# LCD_board.net
KiCad netlist of a schematic drawn in Altium Designer
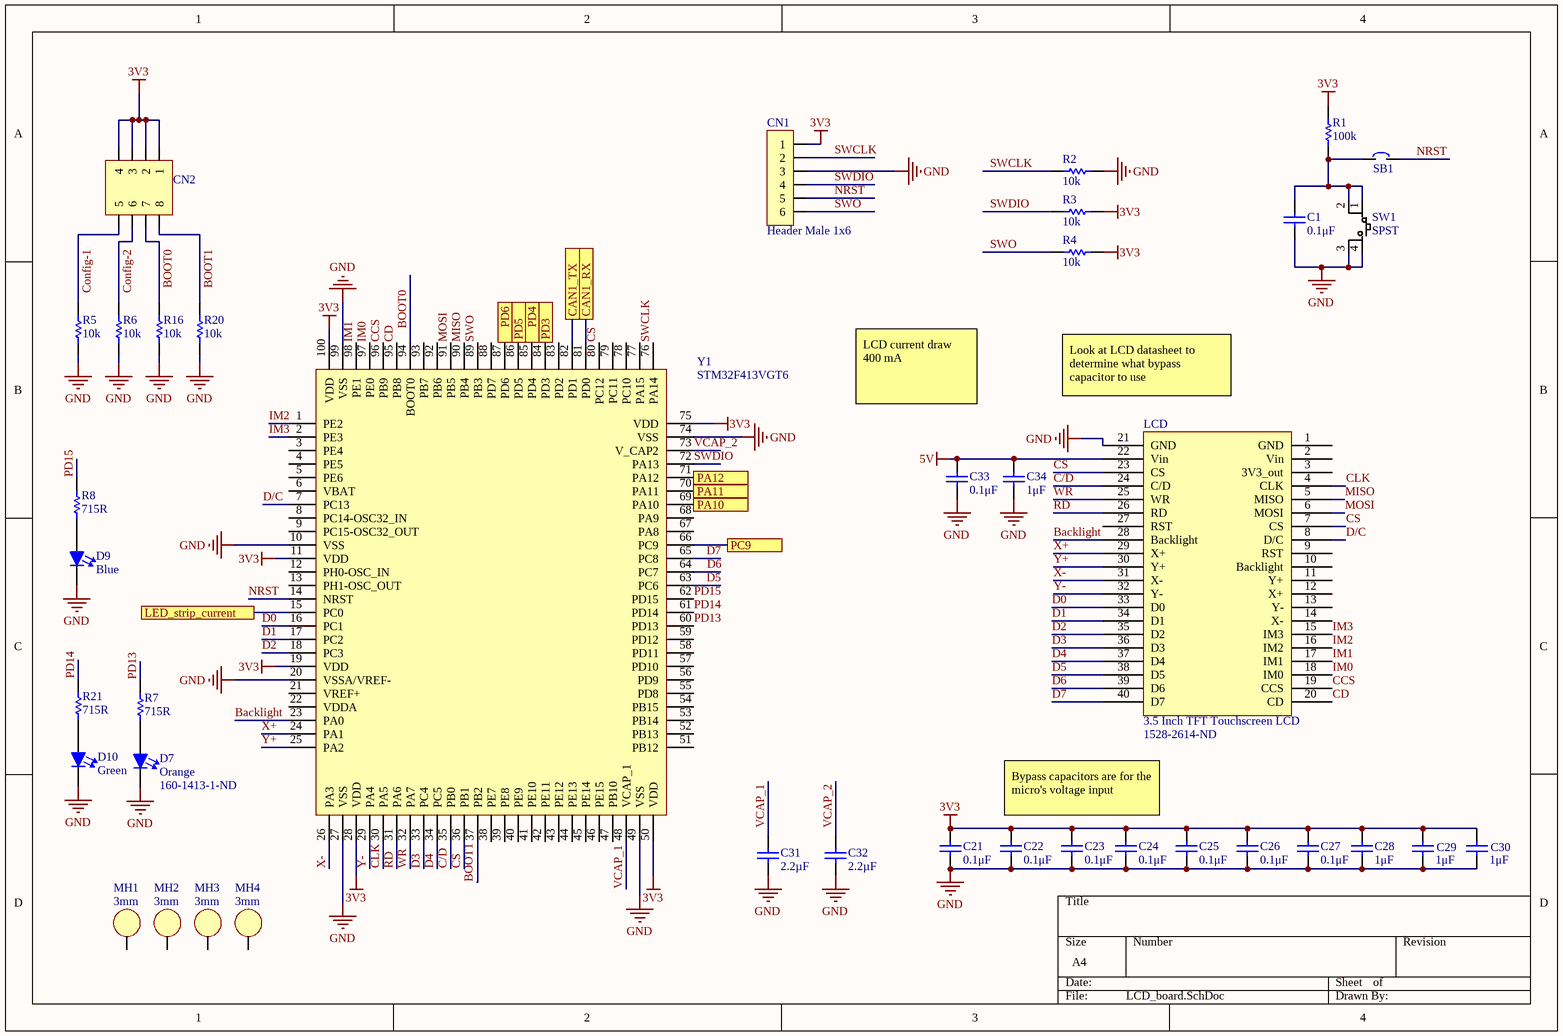
[diagram p0: LCD_board.SchDoc]

(export (version "E")
  (design (tool "Eeschema 10.0.6"))
  (components
    (comp (ref "C1")
      (value "0.1μF")
      (footprint "CAPC1608N(0603\")")
      (description "Capacitor, Ceramic, 100V, +/- 10%, 0603 SMD, X7R")
      (fields
        (field (name "MFG") "TDK")
        (field (name "PUBLISHER") "AUVic")
        (field (name "CREATED BY") "Ashwin Sira")
      )
      (libsource (lib "AUVic_Integrated_Library_Capacitors") (part "0.1uF 100V 0603 SMD, Ceramic"))
    )
    (comp (ref "C21")
      (value "0.1μF")
      (footprint "CAPC1608N(0603\")")
      (description "Capacitor, Ceramic, 100V, +/- 10%, 0603 SMD, X7R")
      (fields
        (field (name "MFG") "TDK")
        (field (name "PUBLISHER") "AUVic")
        (field (name "CREATED BY") "Ashwin Sira")
      )
      (libsource (lib "AUVic_Integrated_Library_Capacitors") (part "0.1uF 100V 0603 SMD, Ceramic"))
    )
    (comp (ref "C22")
      (value "0.1μF")
      (footprint "CAPC1608N(0603\")")
      (description "Capacitor, Ceramic, 100V, +/- 10%, 0603 SMD, X7R")
      (fields
        (field (name "MFG") "TDK")
        (field (name "PUBLISHER") "AUVic")
        (field (name "CREATED BY") "Ashwin Sira")
      )
      (libsource (lib "AUVic_Integrated_Library_Capacitors") (part "0.1uF 100V 0603 SMD, Ceramic"))
    )
    (comp (ref "C23")
      (value "0.1μF")
      (footprint "CAPC1608N(0603\")")
      (description "Capacitor, Ceramic, 100V, +/- 10%, 0603 SMD, X7R")
      (fields
        (field (name "MFG") "TDK")
        (field (name "PUBLISHER") "AUVic")
        (field (name "CREATED BY") "Ashwin Sira")
      )
      (libsource (lib "AUVic_Integrated_Library_Capacitors") (part "0.1uF 100V 0603 SMD, Ceramic"))
    )
    (comp (ref "C24")
      (value "0.1μF")
      (footprint "CAPC1608N(0603\")")
      (description "Capacitor, Ceramic, 100V, +/- 10%, 0603 SMD, X7R")
      (fields
        (field (name "MFG") "TDK")
        (field (name "PUBLISHER") "AUVic")
        (field (name "CREATED BY") "Ashwin Sira")
      )
      (libsource (lib "AUVic_Integrated_Library_Capacitors") (part "0.1uF 100V 0603 SMD, Ceramic"))
    )
    (comp (ref "C25")
      (value "0.1μF")
      (footprint "CAPC1608N(0603\")")
      (description "Capacitor, Ceramic, 100V, +/- 10%, 0603 SMD, X7R")
      (fields
        (field (name "MFG") "TDK")
        (field (name "PUBLISHER") "AUVic")
        (field (name "CREATED BY") "Ashwin Sira")
      )
      (libsource (lib "AUVic_Integrated_Library_Capacitors") (part "0.1uF 100V 0603 SMD, Ceramic"))
    )
    (comp (ref "C26")
      (value "0.1μF")
      (footprint "CAPC1608N(0603\")")
      (description "Capacitor, Ceramic, 100V, +/- 10%, 0603 SMD, X7R")
      (fields
        (field (name "MFG") "TDK")
        (field (name "PUBLISHER") "AUVic")
        (field (name "CREATED BY") "Ashwin Sira")
      )
      (libsource (lib "AUVic_Integrated_Library_Capacitors") (part "0.1uF 100V 0603 SMD, Ceramic"))
    )
    (comp (ref "C27")
      (value "0.1μF")
      (footprint "CAPC1608N(0603\")")
      (description "Capacitor, Ceramic, 100V, +/- 10%, 0603 SMD, X7R")
      (fields
        (field (name "MFG") "TDK")
        (field (name "PUBLISHER") "AUVic")
        (field (name "CREATED BY") "Ashwin Sira")
      )
      (libsource (lib "AUVic_Integrated_Library_Capacitors") (part "0.1uF 100V 0603 SMD, Ceramic"))
    )
    (comp (ref "C28")
      (value "1μF")
      (footprint "CAPC1608N(0603\")")
      (description "Capacitor, Ceramic, 25V, +/- 10%, 0603 SMD, X5R")
      (fields
        (field (name "MFG") "Murata-Electronics-North-America")
        (field (name "PUBLISHER") "AUVic")
        (field (name "CREATED BY") "Andy Bates")
      )
      (libsource (lib "AUVic_Integrated_Library_Capacitors") (part "1uF 25V 0603 SMD, Ceramic"))
    )
    (comp (ref "C29")
      (value "1μF")
      (footprint "CAPC1608N(0603\")")
      (description "Capacitor, Ceramic, 25V, +/- 10%, 0603 SMD, X5R")
      (fields
        (field (name "MFG") "Murata-Electronics-North-America")
        (field (name "PUBLISHER") "AUVic")
        (field (name "CREATED BY") "Andy Bates")
      )
      (libsource (lib "AUVic_Integrated_Library_Capacitors") (part "1uF 25V 0603 SMD, Ceramic"))
    )
    (comp (ref "C30")
      (value "1μF")
      (footprint "CAPC1608N(0603\")")
      (description "Capacitor, Ceramic, 25V, +/- 10%, 0603 SMD, X5R")
      (fields
        (field (name "MFG") "Murata-Electronics-North-America")
        (field (name "PUBLISHER") "AUVic")
        (field (name "CREATED BY") "Andy Bates")
      )
      (libsource (lib "AUVic_Integrated_Library_Capacitors") (part "1uF 25V 0603 SMD, Ceramic"))
    )
    (comp (ref "C31")
      (value "2.2µF")
      (footprint "CAPC1608N(0603\")")
      (description "Capacitor, Ceramic, 50V, 10%, 0603 SMD, X5R")
      (fields (field (name "MADE BY") "*") (field (name "PUBLISHER") "AUVic"))
      (libsource (lib "AUVic_Integrated_Library_Capacitors") (part "2.2uF, 50V, 0603 SMD, X5R, Ceramic"))
    )
    (comp (ref "C32")
      (value "2.2µF")
      (footprint "CAPC1608N(0603\")")
      (description "Capacitor, Ceramic, 50V, 10%, 0603 SMD, X5R")
      (fields (field (name "MADE BY") "*") (field (name "PUBLISHER") "AUVic"))
      (libsource (lib "AUVic_Integrated_Library_Capacitors") (part "2.2uF, 50V, 0603 SMD, X5R, Ceramic"))
    )
    (comp (ref "C33")
      (value "0.1μF")
      (footprint "CAPC1608N(0603\")")
      (description "Capacitor, Ceramic, 100V, +/- 10%, 0603 SMD, X7R")
      (fields
        (field (name "MFG") "TDK")
        (field (name "PUBLISHER") "AUVic")
        (field (name "CREATED BY") "Ashwin Sira")
      )
      (libsource (lib "AUVic_Integrated_Library_Capacitors") (part "0.1uF 100V 0603 SMD, Ceramic"))
    )
    (comp (ref "C34")
      (value "1μF")
      (footprint "CAPC1608N(0603\")")
      (description "Capacitor, Ceramic, 25V, +/- 10%, 0603 SMD, X5R")
      (fields
        (field (name "MFG") "Murata-Electronics-North-America")
        (field (name "PUBLISHER") "AUVic")
        (field (name "CREATED BY") "Andy Bates")
      )
      (libsource (lib "AUVic_Integrated_Library_Capacitors") (part "1uF 25V 0603 SMD, Ceramic"))
    )
    (comp (ref "CN1")
      (value "Header Male 1x6")
      (footprint "Header, Male, 1X6")
      (description "1x6, Pads Pitch: 0.1\" (2.54mm), Through hole")
      (libsource (lib "AUVic_Integrated_Library_Connectors") (part "Header, Male, 1x6"))
    )
    (comp (ref "CN2")
      (value "Header, Male, 2x4, Pitch: 0.1\" (2.54mm), THT")
      (footprint "Header, Male, 2x4, Pitch: 0.1\" (2.54mm),THT")
      (fields
        (field (name "PUBLISHER") "AUVic")
        (field (name "REVIEWED BY") "*")
        (field (name "CREATED BY") "Andy Bates")
      )
      (libsource (lib "AUVic_Integrated_Library_Connectors") (part "Header, Male, 2x4, Pitch{colon} 0.1{dblquote} (2.54mm), THT"))
    )
    (comp (ref "D7")
      (value "Orange")
      (footprint "LED0805")
      (description "LED, 0805 (2012), Orange, Clear")
      (fields
        (field (name "SUPPLIER PART NUMBER 1") "160-1413-1-ND")
        (field (name "CREATED BY") "Robert Keen")
      )
      (libsource (lib "AUVic_Integrated_Library_Diodes") (part "LED, 0805 (2012), Orange, Clear"))
    )
    (comp (ref "D9")
      (value "Blue")
      (footprint "LED0805")
      (description "LED, 0805 (2012), Blue, Clear")
      (fields (field (name "CREATED BY") "Ashwin Sira"))
      (libsource (lib "AUVic_Integrated_Library_Diodes") (part "LED, 0805 (2012), Blue, Clear"))
    )
    (comp (ref "D10")
      (value "Green")
      (footprint "LED0805")
      (description "LED, 0805 (2012), Green, Clear")
      (fields (field (name "CREATED BY") "Andy Bates"))
      (libsource (lib "AUVic_Integrated_Library_Diodes") (part "LED, 0805 (2012), Green, Clear"))
    )
    (comp (ref "LCD")
      (value "3.5 Inch TFT Touchscreen LCD")
      (footprint "LCD_touchscreen_tft")
      (description "3.2\" TFT LCD with Touchscreen Breakout Board w/MicroSD Socket")
      (fields (field (name "SUPPLIER PART NUMBER 1") "1528-2614-ND"))
      (libsource (lib "AUVic_Integrated_Library_LCDs") (part "Adafruit ILI9341"))
    )
    (comp (ref "MH1")
      (value "3mm")
      (footprint "Mount-Hole_3mm")
      (libsource (lib "AUVic_Integrated_Library_Connectors") (part "Mount_Hole_3mm"))
    )
    (comp (ref "MH2")
      (value "3mm")
      (footprint "Mount-Hole_3mm")
      (libsource (lib "AUVic_Integrated_Library_Connectors") (part "Mount_Hole_3mm"))
    )
    (comp (ref "MH3")
      (value "3mm")
      (footprint "Mount-Hole_3mm")
      (libsource (lib "AUVic_Integrated_Library_Connectors") (part "Mount_Hole_3mm"))
    )
    (comp (ref "MH4")
      (value "3mm")
      (footprint "Mount-Hole_3mm")
      (libsource (lib "AUVic_Integrated_Library_Connectors") (part "Mount_Hole_3mm"))
    )
    (comp (ref "R1")
      (value "100k")
      (footprint "RESC1608N(0603\")")
      (description "100kR, 1%, 1/10W, 0603 SMD")
      (fields (field (name "MADE BY") "Andy Bates"))
      (libsource (lib "AUVic_Integrated_Library_Resistors") (part "100kR, 1%, 1/10W, 0603 SMD"))
    )
    (comp (ref "R2")
      (value "10k")
      (footprint "RESC1608N(0603\")")
      (description "10kR, 1%, 1/10W, 0603 SMD")
      (fields (field (name "MADE BY") "Ashwin Sira"))
      (libsource (lib "AUVic_Integrated_Library_Resistors") (part "10kR, 1%, 1/10W, 0603 SMD"))
    )
    (comp (ref "R3")
      (value "10k")
      (footprint "RESC1608N(0603\")")
      (description "10kR, 1%, 1/10W, 0603 SMD")
      (fields (field (name "MADE BY") "Ashwin Sira"))
      (libsource (lib "AUVic_Integrated_Library_Resistors") (part "10kR, 1%, 1/10W, 0603 SMD"))
    )
    (comp (ref "R4")
      (value "10k")
      (footprint "RESC1608N(0603\")")
      (description "10kR, 1%, 1/10W, 0603 SMD")
      (fields (field (name "MADE BY") "Ashwin Sira"))
      (libsource (lib "AUVic_Integrated_Library_Resistors") (part "10kR, 1%, 1/10W, 0603 SMD"))
    )
    (comp (ref "R5")
      (value "10k")
      (footprint "RESC1608N(0603\")")
      (description "10kR, 1%, 1/10W, 0603 SMD")
      (fields (field (name "MADE BY") "Ashwin Sira"))
      (libsource (lib "AUVic_Integrated_Library_Resistors") (part "10kR, 1%, 1/10W, 0603 SMD"))
    )
    (comp (ref "R6")
      (value "10k")
      (footprint "RESC1608N(0603\")")
      (description "10kR, 1%, 1/10W, 0603 SMD")
      (fields (field (name "MADE BY") "Ashwin Sira"))
      (libsource (lib "AUVic_Integrated_Library_Resistors") (part "10kR, 1%, 1/10W, 0603 SMD"))
    )
    (comp (ref "R7")
      (value "715R")
      (footprint "RESC1608N(0603\")")
      (description "715R, 1%, 1/10W, 0603, SMD")
      (fields (field (name "CREATED BY") "Ashwin Sira") (field (name "PUBLISHER") "AUVic"))
      (libsource (lib "AUVic_Integrated_Library_Resistors") (part "715R, 1%, 1/10W, 0603, SMD"))
    )
    (comp (ref "R8")
      (value "715R")
      (footprint "RESC1608N(0603\")")
      (description "715R, 1%, 1/10W, 0603, SMD")
      (fields (field (name "CREATED BY") "Ashwin Sira") (field (name "PUBLISHER") "AUVic"))
      (libsource (lib "AUVic_Integrated_Library_Resistors") (part "715R, 1%, 1/10W, 0603, SMD"))
    )
    (comp (ref "R16")
      (value "10k")
      (footprint "RESC1608N(0603\")")
      (description "10kR, 1%, 1/10W, 0603 SMD")
      (fields (field (name "MADE BY") "Ashwin Sira"))
      (libsource (lib "AUVic_Integrated_Library_Resistors") (part "10kR, 1%, 1/10W, 0603 SMD"))
    )
    (comp (ref "R20")
      (value "10k")
      (footprint "RESC1608N(0603\")")
      (description "10kR, 1%, 1/10W, 0603 SMD")
      (fields (field (name "MADE BY") "Ashwin Sira"))
      (libsource (lib "AUVic_Integrated_Library_Resistors") (part "10kR, 1%, 1/10W, 0603 SMD"))
    )
    (comp (ref "R21")
      (value "715R")
      (footprint "RESC1608N(0603\")")
      (description "715R, 1%, 1/10W, 0603, SMD")
      (fields (field (name "CREATED BY") "Ashwin Sira") (field (name "PUBLISHER") "AUVic"))
      (libsource (lib "AUVic_Integrated_Library_Resistors") (part "715R, 1%, 1/10W, 0603, SMD"))
    )
    (comp (ref "SB1")
      (value "Solder Bridge")
      (footprint "Solder Bridge")
      (fields (field (name "MADE BY") "Andy Bates"))
      (libsource (lib "AUVic_Integrated_Library_Connectors") (part "Solder Bridge"))
    )
    (comp (ref "SW1")
      (value "SPST")
      (footprint "4-SPST-NO")
      (fields (field (name "MADE BY") "Andy Bates"))
      (libsource (lib "AUVic_Integrated_Library_Switches") (part "4 pin Tacitle Switch"))
    )
    (comp (ref "Y1")
      (value "STM32F413VGT6")
      (footprint "STM-LQFP100_M")
      (description "ARM Cortex-M4 32-bit MCU, 180 MHz, 320 KB Internal Rap, 81 I/O, 100-pin LQFP, -40 to 85 degC, Tray")
      (libsource (lib "AUVic_Integrated_Library_Microprocessors") (part "STM32F413VGT6"))
    )
  )
  (nets
    (net (code "1") (name "/BOOT0") (class "Default")
      (node (ref "CN2") (pin "7") (pinfunction "7_7") (pintype "passive"))
      (node (ref "R16") (pin "2") (pinfunction "2_2") (pintype "passive"))
      (node (ref "Y1") (pin "94") (pinfunction "BOOT0_94") (pintype "passive"))
    )
    (net (code "2") (name "/BOOT1") (class "Default")
      (node (ref "CN2") (pin "8") (pinfunction "8_8") (pintype "passive"))
      (node (ref "R20") (pin "2") (pinfunction "2_2") (pintype "passive"))
      (node (ref "Y1") (pin "37") (pinfunction "PB2_37") (pintype "passive"))
    )
    (net (code "3") (name "/Backlight") (class "Default")
      (node (ref "LCD") (pin "28") (pinfunction "Backlight_28") (pintype "passive"))
      (node (ref "Y1") (pin "23") (pinfunction "PA0_23") (pintype "passive"))
    )
    (net (code "4") (name "/CAN1_RX") (class "Default")
      (node (ref "Y1") (pin "81") (pinfunction "PD0_81") (pintype "passive"))
    )
    (net (code "5") (name "/CAN1_TX") (class "Default")
      (node (ref "Y1") (pin "82") (pinfunction "PD1_82") (pintype "passive"))
    )
    (net (code "6") (name "/CCS") (class "Default")
      (node (ref "LCD") (pin "19") (pinfunction "CCS_19") (pintype "passive"))
      (node (ref "Y1") (pin "96") (pinfunction "PB9_96") (pintype "passive"))
    )
    (net (code "7") (name "/CD") (class "Default")
      (node (ref "LCD") (pin "20") (pinfunction "CD_20") (pintype "passive"))
      (node (ref "Y1") (pin "95") (pinfunction "PB8_95") (pintype "passive"))
    )
    (net (code "8") (name "/CLK") (class "Default")
      (node (ref "LCD") (pin "4") (pinfunction "CLK_4") (pintype "passive"))
      (node (ref "Y1") (pin "30") (pinfunction "PA5_30") (pintype "passive"))
    )
    (net (code "9") (name "/CS") (class "Default")
      (node (ref "LCD") (pin "23") (pinfunction "CS_23") (pintype "passive"))
      (node (ref "LCD") (pin "7") (pinfunction "CS_7") (pintype "passive"))
      (node (ref "Y1") (pin "36") (pinfunction "PB1_36") (pintype "passive"))
      (node (ref "Y1") (pin "80") (pinfunction "PC12_80") (pintype "passive"))
    )
    (net (code "10") (name "/Config-1") (class "Default")
      (node (ref "CN2") (pin "5") (pinfunction "5_5") (pintype "passive"))
      (node (ref "R5") (pin "2") (pinfunction "2_2") (pintype "passive"))
    )
    (net (code "11") (name "/Config-2") (class "Default")
      (node (ref "CN2") (pin "6") (pinfunction "6_6") (pintype "passive"))
      (node (ref "R6") (pin "2") (pinfunction "2_2") (pintype "passive"))
    )
    (net (code "12") (name "/C{slash}D") (class "Default")
      (node (ref "LCD") (pin "24") (pinfunction "C/D_24") (pintype "passive"))
      (node (ref "Y1") (pin "35") (pinfunction "PB0_35") (pintype "passive"))
    )
    (net (code "13") (name "/D0") (class "Default")
      (node (ref "LCD") (pin "33") (pinfunction "D0_33") (pintype "passive"))
      (node (ref "Y1") (pin "16") (pinfunction "PC1_16") (pintype "passive"))
    )
    (net (code "14") (name "/D1") (class "Default")
      (node (ref "LCD") (pin "34") (pinfunction "D1_34") (pintype "passive"))
      (node (ref "Y1") (pin "17") (pinfunction "PC2_17") (pintype "passive"))
    )
    (net (code "15") (name "/D2") (class "Default")
      (node (ref "LCD") (pin "35") (pinfunction "D2_35") (pintype "passive"))
      (node (ref "Y1") (pin "18") (pinfunction "PC3_18") (pintype "passive"))
    )
    (net (code "16") (name "/D3") (class "Default")
      (node (ref "LCD") (pin "36") (pinfunction "D3_36") (pintype "passive"))
      (node (ref "Y1") (pin "33") (pinfunction "PC4_33") (pintype "passive"))
    )
    (net (code "17") (name "/D4") (class "Default")
      (node (ref "LCD") (pin "37") (pinfunction "D4_37") (pintype "passive"))
      (node (ref "Y1") (pin "34") (pinfunction "PC5_34") (pintype "passive"))
    )
    (net (code "18") (name "/D5") (class "Default")
      (node (ref "LCD") (pin "38") (pinfunction "D5_38") (pintype "passive"))
      (node (ref "Y1") (pin "63") (pinfunction "PC6_63") (pintype "passive"))
    )
    (net (code "19") (name "/D6") (class "Default")
      (node (ref "LCD") (pin "39") (pinfunction "D6_39") (pintype "passive"))
      (node (ref "Y1") (pin "64") (pinfunction "PC7_64") (pintype "passive"))
    )
    (net (code "20") (name "/D7") (class "Default")
      (node (ref "LCD") (pin "40") (pinfunction "D7_40") (pintype "passive"))
      (node (ref "Y1") (pin "65") (pinfunction "PC8_65") (pintype "passive"))
    )
    (net (code "21") (name "/D{slash}C") (class "Default")
      (node (ref "LCD") (pin "8") (pinfunction "D/C_8") (pintype "passive"))
      (node (ref "Y1") (pin "7") (pinfunction "PC13_7") (pintype "passive"))
    )
    (net (code "22") (name "/IM0") (class "Default")
      (node (ref "LCD") (pin "18") (pinfunction "IM0_18") (pintype "passive"))
      (node (ref "Y1") (pin "97") (pinfunction "PE0_97") (pintype "passive"))
    )
    (net (code "23") (name "/IM1") (class "Default")
      (node (ref "LCD") (pin "17") (pinfunction "IM1_17") (pintype "passive"))
      (node (ref "Y1") (pin "98") (pinfunction "PE1_98") (pintype "passive"))
    )
    (net (code "24") (name "/IM2") (class "Default")
      (node (ref "LCD") (pin "16") (pinfunction "IM2_16") (pintype "passive"))
      (node (ref "Y1") (pin "1") (pinfunction "PE2_1") (pintype "passive"))
    )
    (net (code "25") (name "/IM3") (class "Default")
      (node (ref "LCD") (pin "15") (pinfunction "IM3_15") (pintype "passive"))
      (node (ref "Y1") (pin "2") (pinfunction "PE3_2") (pintype "passive"))
    )
    (net (code "26") (name "/LED_strip_current") (class "Default")
      (node (ref "Y1") (pin "15") (pinfunction "PC0_15") (pintype "passive"))
    )
    (net (code "27") (name "/MISO") (class "Default")
      (node (ref "LCD") (pin "5") (pinfunction "MISO_5") (pintype "passive"))
      (node (ref "Y1") (pin "90") (pinfunction "PB4_90") (pintype "passive"))
    )
    (net (code "28") (name "/MOSI") (class "Default")
      (node (ref "LCD") (pin "6") (pinfunction "MOSI_6") (pintype "passive"))
      (node (ref "Y1") (pin "91") (pinfunction "PB5_91") (pintype "passive"))
    )
    (net (code "29") (name "/NRST") (class "Default")
      (node (ref "CN1") (pin "5") (pinfunction "5_5") (pintype "passive"))
      (node (ref "SB1") (pin "2") (pinfunction "2_2") (pintype "passive"))
      (node (ref "Y1") (pin "14") (pinfunction "NRST_14") (pintype "passive"))
    )
    (net (code "30") (name "/PA10") (class "Default")
      (node (ref "Y1") (pin "69") (pinfunction "PA10_69") (pintype "passive"))
    )
    (net (code "31") (name "/PA11") (class "Default")
      (node (ref "Y1") (pin "70") (pinfunction "PA11_70") (pintype "passive"))
    )
    (net (code "32") (name "/PA12") (class "Default")
      (node (ref "Y1") (pin "71") (pinfunction "PA12_71") (pintype "passive"))
    )
    (net (code "33") (name "/PC9") (class "Default")
      (node (ref "Y1") (pin "66") (pinfunction "PC9_66") (pintype "passive"))
    )
    (net (code "34") (name "/PD3") (class "Default")
      (node (ref "Y1") (pin "84") (pinfunction "PD3_84") (pintype "passive"))
    )
    (net (code "35") (name "/PD4") (class "Default")
      (node (ref "Y1") (pin "85") (pinfunction "PD4_85") (pintype "passive"))
    )
    (net (code "36") (name "/PD5") (class "Default")
      (node (ref "Y1") (pin "86") (pinfunction "PD5_86") (pintype "passive"))
    )
    (net (code "37") (name "/PD6") (class "Default")
      (node (ref "Y1") (pin "87") (pinfunction "PD6_87") (pintype "passive"))
    )
    (net (code "38") (name "/PD13") (class "Default")
      (node (ref "R7") (pin "2") (pinfunction "2_2") (pintype "passive"))
      (node (ref "Y1") (pin "60") (pinfunction "PD13_60") (pintype "passive"))
    )
    (net (code "39") (name "/PD14") (class "Default")
      (node (ref "R21") (pin "2") (pinfunction "2_2") (pintype "passive"))
      (node (ref "Y1") (pin "61") (pinfunction "PD14_61") (pintype "passive"))
    )
    (net (code "40") (name "/PD15") (class "Default")
      (node (ref "R8") (pin "2") (pinfunction "2_2") (pintype "passive"))
      (node (ref "Y1") (pin "62") (pinfunction "PD15_62") (pintype "passive"))
    )
    (net (code "41") (name "/RD") (class "Default")
      (node (ref "LCD") (pin "26") (pinfunction "RD_26") (pintype "passive"))
      (node (ref "Y1") (pin "31") (pinfunction "PA6_31") (pintype "passive"))
    )
    (net (code "42") (name "/SWCLK") (class "Default")
      (node (ref "CN1") (pin "2") (pinfunction "2_2") (pintype "passive"))
      (node (ref "R2") (pin "2") (pinfunction "2_2") (pintype "passive"))
      (node (ref "Y1") (pin "76") (pinfunction "PA14_76") (pintype "passive"))
    )
    (net (code "43") (name "/SWDIO") (class "Default")
      (node (ref "CN1") (pin "4") (pinfunction "4_4") (pintype "passive"))
      (node (ref "R3") (pin "1") (pinfunction "1_1") (pintype "passive"))
      (node (ref "Y1") (pin "72") (pinfunction "PA13_72") (pintype "passive"))
    )
    (net (code "44") (name "/SWO") (class "Default")
      (node (ref "CN1") (pin "6") (pinfunction "6_6") (pintype "passive"))
      (node (ref "R4") (pin "1") (pinfunction "1_1") (pintype "passive"))
      (node (ref "Y1") (pin "89") (pinfunction "PB3_89") (pintype "passive"))
    )
    (net (code "45") (name "/VCAP_1") (class "Default")
      (node (ref "C31") (pin "2") (pinfunction "Cathode_2") (pintype "passive"))
      (node (ref "Y1") (pin "48") (pinfunction "VCAP_1_48") (pintype "passive"))
    )
    (net (code "46") (name "/VCAP_2") (class "Default")
      (node (ref "C32") (pin "2") (pinfunction "Cathode_2") (pintype "passive"))
      (node (ref "Y1") (pin "73") (pinfunction "V_CAP2_73") (pintype "passive"))
    )
    (net (code "47") (name "/WR") (class "Default")
      (node (ref "LCD") (pin "25") (pinfunction "WR_25") (pintype "passive"))
      (node (ref "Y1") (pin "32") (pinfunction "PA7_32") (pintype "passive"))
    )
    (net (code "48") (name "/X+") (class "Default")
      (node (ref "LCD") (pin "29") (pinfunction "X+_29") (pintype "passive"))
      (node (ref "Y1") (pin "24") (pinfunction "PA1_24") (pintype "passive"))
    )
    (net (code "49") (name "/X-") (class "Default")
      (node (ref "LCD") (pin "31") (pinfunction "X-_31") (pintype "passive"))
      (node (ref "Y1") (pin "26") (pinfunction "PA3_26") (pintype "passive"))
    )
    (net (code "50") (name "/Y+") (class "Default")
      (node (ref "LCD") (pin "30") (pinfunction "Y+_30") (pintype "passive"))
      (node (ref "Y1") (pin "25") (pinfunction "PA2_25") (pintype "passive"))
    )
    (net (code "51") (name "/Y-") (class "Default")
      (node (ref "LCD") (pin "32") (pinfunction "Y-_32") (pintype "passive"))
      (node (ref "Y1") (pin "29") (pinfunction "PA4_29") (pintype "passive"))
    )
    (net (code "52") (name "3V3") (class "Default")
      (node (ref "C21") (pin "2") (pinfunction "Cathode_2") (pintype "passive"))
      (node (ref "C22") (pin "2") (pinfunction "Cathode_2") (pintype "passive"))
      (node (ref "C23") (pin "2") (pinfunction "Cathode_2") (pintype "passive"))
      (node (ref "C24") (pin "2") (pinfunction "Cathode_2") (pintype "passive"))
      (node (ref "C25") (pin "2") (pinfunction "Cathode_2") (pintype "passive"))
      (node (ref "C26") (pin "2") (pinfunction "Cathode_2") (pintype "passive"))
      (node (ref "C27") (pin "2") (pinfunction "Cathode_2") (pintype "passive"))
      (node (ref "C28") (pin "2") (pinfunction "Cathode_2") (pintype "passive"))
      (node (ref "C29") (pin "2") (pinfunction "Cathode_2") (pintype "passive"))
      (node (ref "C30") (pin "2") (pinfunction "Cathode_2") (pintype "passive"))
      (node (ref "CN1") (pin "1") (pinfunction "1_1") (pintype "passive"))
      (node (ref "CN2") (pin "1") (pinfunction "1_1") (pintype "passive"))
      (node (ref "CN2") (pin "2") (pinfunction "2_2") (pintype "passive"))
      (node (ref "CN2") (pin "3") (pinfunction "3_3") (pintype "passive"))
      (node (ref "CN2") (pin "4") (pinfunction "4_4") (pintype "passive"))
      (node (ref "R1") (pin "2") (pinfunction "2_2") (pintype "passive"))
      (node (ref "R3") (pin "2") (pinfunction "2_2") (pintype "passive"))
      (node (ref "R4") (pin "2") (pinfunction "2_2") (pintype "passive"))
      (node (ref "Y1") (pin "100") (pinfunction "VDD_100") (pintype "passive"))
      (node (ref "Y1") (pin "11") (pinfunction "VDD_11") (pintype "passive"))
      (node (ref "Y1") (pin "19") (pinfunction "VDD_19") (pintype "passive"))
      (node (ref "Y1") (pin "28") (pinfunction "VDD_28") (pintype "passive"))
      (node (ref "Y1") (pin "50") (pinfunction "VDD_50") (pintype "passive"))
      (node (ref "Y1") (pin "75") (pinfunction "VDD_75") (pintype "passive"))
    )
    (net (code "53") (name "5V") (class "Default")
      (node (ref "C33") (pin "2") (pinfunction "Cathode_2") (pintype "passive"))
      (node (ref "C34") (pin "2") (pinfunction "Cathode_2") (pintype "passive"))
      (node (ref "LCD") (pin "22") (pinfunction "Vin_22") (pintype "passive"))
    )
    (net (code "54") (name "GND") (class "Default")
      (node (ref "C1") (pin "1") (pinfunction "Anode_1") (pintype "passive"))
      (node (ref "C21") (pin "1") (pinfunction "Anode_1") (pintype "passive"))
      (node (ref "C22") (pin "1") (pinfunction "Anode_1") (pintype "passive"))
      (node (ref "C23") (pin "1") (pinfunction "Anode_1") (pintype "passive"))
      (node (ref "C24") (pin "1") (pinfunction "Anode_1") (pintype "passive"))
      (node (ref "C25") (pin "1") (pinfunction "Anode_1") (pintype "passive"))
      (node (ref "C26") (pin "1") (pinfunction "Anode_1") (pintype "passive"))
      (node (ref "C27") (pin "1") (pinfunction "Anode_1") (pintype "passive"))
      (node (ref "C28") (pin "1") (pinfunction "Anode_1") (pintype "passive"))
      (node (ref "C29") (pin "1") (pinfunction "Anode_1") (pintype "passive"))
      (node (ref "C30") (pin "1") (pinfunction "Anode_1") (pintype "passive"))
      (node (ref "C31") (pin "1") (pinfunction "Anode_1") (pintype "passive"))
      (node (ref "C32") (pin "1") (pinfunction "Anode_1") (pintype "passive"))
      (node (ref "C33") (pin "1") (pinfunction "Anode_1") (pintype "passive"))
      (node (ref "C34") (pin "1") (pinfunction "Anode_1") (pintype "passive"))
      (node (ref "CN1") (pin "3") (pinfunction "3_3") (pintype "passive"))
      (node (ref "D10") (pin "1") (pinfunction "Cathode_1") (pintype "passive"))
      (node (ref "D7") (pin "1") (pinfunction "Cathode_1") (pintype "passive"))
      (node (ref "D9") (pin "1") (pinfunction "Cathode_1") (pintype "passive"))
      (node (ref "LCD") (pin "21") (pinfunction "GND_21") (pintype "passive"))
      (node (ref "R16") (pin "1") (pinfunction "1_1") (pintype "passive"))
      (node (ref "R2") (pin "1") (pinfunction "1_1") (pintype "passive"))
      (node (ref "R20") (pin "1") (pinfunction "1_1") (pintype "passive"))
      (node (ref "R5") (pin "1") (pinfunction "1_1") (pintype "passive"))
      (node (ref "R6") (pin "1") (pinfunction "1_1") (pintype "passive"))
      (node (ref "SW1") (pin "3") (pinfunction "3_3") (pintype "passive"))
      (node (ref "SW1") (pin "4") (pinfunction "4_4") (pintype "passive"))
      (node (ref "Y1") (pin "10") (pinfunction "VSS_10") (pintype "passive"))
      (node (ref "Y1") (pin "20") (pinfunction "VSSA/VREF-_20") (pintype "passive"))
      (node (ref "Y1") (pin "27") (pinfunction "VSS_27") (pintype "passive"))
      (node (ref "Y1") (pin "49") (pinfunction "VSS_49") (pintype "passive"))
      (node (ref "Y1") (pin "74") (pinfunction "VSS_74") (pintype "passive"))
      (node (ref "Y1") (pin "99") (pinfunction "VSS_99") (pintype "passive"))
    )
    (net (code "55") (name "Net-(C1-Cathode)") (class "Default")
      (node (ref "C1") (pin "2") (pinfunction "Cathode_2") (pintype "passive"))
      (node (ref "R1") (pin "1") (pinfunction "1_1") (pintype "passive"))
      (node (ref "SB1") (pin "1") (pinfunction "1_1") (pintype "passive"))
      (node (ref "SW1") (pin "1") (pinfunction "1_1") (pintype "passive"))
      (node (ref "SW1") (pin "2") (pinfunction "2_2") (pintype "passive"))
    )
    (net (code "56") (name "Net-(D7-Anode)") (class "Default")
      (node (ref "D7") (pin "2") (pinfunction "Anode_2") (pintype "passive"))
      (node (ref "R7") (pin "1") (pinfunction "1_1") (pintype "passive"))
    )
    (net (code "57") (name "Net-(D9-Anode)") (class "Default")
      (node (ref "D9") (pin "2") (pinfunction "Anode_2") (pintype "passive"))
      (node (ref "R8") (pin "1") (pinfunction "1_1") (pintype "passive"))
    )
    (net (code "58") (name "Net-(D10-Anode)") (class "Default")
      (node (ref "D10") (pin "2") (pinfunction "Anode_2") (pintype "passive"))
      (node (ref "R21") (pin "1") (pinfunction "1_1") (pintype "passive"))
    )
    (net (code "59") (name "unconnected-(LCD-3V3_out-Pad3)") (class "Default")
      (node (ref "LCD") (pin "3") (pinfunction "3V3_out_3") (pintype "passive"))
    )
    (net (code "60") (name "unconnected-(LCD-Backlight-Pad10)") (class "Default")
      (node (ref "LCD") (pin "10") (pinfunction "Backlight_10") (pintype "passive"))
    )
    (net (code "61") (name "unconnected-(LCD-GND-Pad1)") (class "Default")
      (node (ref "LCD") (pin "1") (pinfunction "GND_1") (pintype "passive"))
    )
    (net (code "62") (name "unconnected-(LCD-RST-Pad9)") (class "Default")
      (node (ref "LCD") (pin "9") (pinfunction "RST_9") (pintype "passive"))
    )
    (net (code "63") (name "unconnected-(LCD-RST-Pad27)") (class "Default")
      (node (ref "LCD") (pin "27") (pinfunction "RST_27") (pintype "passive"))
    )
    (net (code "64") (name "unconnected-(LCD-Vin-Pad2)") (class "Default")
      (node (ref "LCD") (pin "2") (pinfunction "Vin_2") (pintype "passive"))
    )
    (net (code "65") (name "unconnected-(LCD-X+-Pad12)") (class "Default")
      (node (ref "LCD") (pin "12") (pinfunction "X+_12") (pintype "passive"))
    )
    (net (code "66") (name "unconnected-(LCD-X--Pad14)") (class "Default")
      (node (ref "LCD") (pin "14") (pinfunction "X-_14") (pintype "passive"))
    )
    (net (code "67") (name "unconnected-(LCD-Y+-Pad11)") (class "Default")
      (node (ref "LCD") (pin "11") (pinfunction "Y+_11") (pintype "passive"))
    )
    (net (code "68") (name "unconnected-(LCD-Y--Pad13)") (class "Default")
      (node (ref "LCD") (pin "13") (pinfunction "Y-_13") (pintype "passive"))
    )
    (net (code "69") (name "unconnected-(MH1-Pad1)") (class "Default")
      (node (ref "MH1") (pin "1") (pinfunction "1_1") (pintype "passive"))
    )
    (net (code "70") (name "unconnected-(MH2-Pad1)") (class "Default")
      (node (ref "MH2") (pin "1") (pinfunction "1_1") (pintype "passive"))
    )
    (net (code "71") (name "unconnected-(MH3-Pad1)") (class "Default")
      (node (ref "MH3") (pin "1") (pinfunction "1_1") (pintype "passive"))
    )
    (net (code "72") (name "unconnected-(MH4-Pad1)") (class "Default")
      (node (ref "MH4") (pin "1") (pinfunction "1_1") (pintype "passive"))
    )
    (net (code "73") (name "unconnected-(Y1-PA8-Pad67)") (class "Default")
      (node (ref "Y1") (pin "67") (pinfunction "PA8_67") (pintype "passive"))
    )
    (net (code "74") (name "unconnected-(Y1-PA9-Pad68)") (class "Default")
      (node (ref "Y1") (pin "68") (pinfunction "PA9_68") (pintype "passive"))
    )
    (net (code "75") (name "unconnected-(Y1-PA15-Pad77)") (class "Default")
      (node (ref "Y1") (pin "77") (pinfunction "PA15_77") (pintype "passive"))
    )
    (net (code "76") (name "unconnected-(Y1-PB6-Pad92)") (class "Default")
      (node (ref "Y1") (pin "92") (pinfunction "PB6_92") (pintype "passive"))
    )
    (net (code "77") (name "unconnected-(Y1-PB7-Pad93)") (class "Default")
      (node (ref "Y1") (pin "93") (pinfunction "PB7_93") (pintype "passive"))
    )
    (net (code "78") (name "unconnected-(Y1-PB10-Pad47)") (class "Default")
      (node (ref "Y1") (pin "47") (pinfunction "PB10_47") (pintype "passive"))
    )
    (net (code "79") (name "unconnected-(Y1-PB12-Pad51)") (class "Default")
      (node (ref "Y1") (pin "51") (pinfunction "PB12_51") (pintype "passive"))
    )
    (net (code "80") (name "unconnected-(Y1-PB13-Pad52)") (class "Default")
      (node (ref "Y1") (pin "52") (pinfunction "PB13_52") (pintype "passive"))
    )
    (net (code "81") (name "unconnected-(Y1-PB14-Pad53)") (class "Default")
      (node (ref "Y1") (pin "53") (pinfunction "PB14_53") (pintype "passive"))
    )
    (net (code "82") (name "unconnected-(Y1-PB15-Pad54)") (class "Default")
      (node (ref "Y1") (pin "54") (pinfunction "PB15_54") (pintype "passive"))
    )
    (net (code "83") (name "unconnected-(Y1-PC10-Pad78)") (class "Default")
      (node (ref "Y1") (pin "78") (pinfunction "PC10_78") (pintype "passive"))
    )
    (net (code "84") (name "unconnected-(Y1-PC11-Pad79)") (class "Default")
      (node (ref "Y1") (pin "79") (pinfunction "PC11_79") (pintype "passive"))
    )
    (net (code "85") (name "unconnected-(Y1-PC14-OSC32_IN-Pad8)") (class "Default")
      (node (ref "Y1") (pin "8") (pinfunction "PC14-OSC32_IN_8") (pintype "passive"))
    )
    (net (code "86") (name "unconnected-(Y1-PC15-OSC32_OUT-Pad9)") (class "Default")
      (node (ref "Y1") (pin "9") (pinfunction "PC15-OSC32_OUT_9") (pintype "passive"))
    )
    (net (code "87") (name "unconnected-(Y1-PD2-Pad83)") (class "Default")
      (node (ref "Y1") (pin "83") (pinfunction "PD2_83") (pintype "passive"))
    )
    (net (code "88") (name "unconnected-(Y1-PD7-Pad88)") (class "Default")
      (node (ref "Y1") (pin "88") (pinfunction "PD7_88") (pintype "passive"))
    )
    (net (code "89") (name "unconnected-(Y1-PD8-Pad55)") (class "Default")
      (node (ref "Y1") (pin "55") (pinfunction "PD8_55") (pintype "passive"))
    )
    (net (code "90") (name "unconnected-(Y1-PD9-Pad56)") (class "Default")
      (node (ref "Y1") (pin "56") (pinfunction "PD9_56") (pintype "passive"))
    )
    (net (code "91") (name "unconnected-(Y1-PD10-Pad57)") (class "Default")
      (node (ref "Y1") (pin "57") (pinfunction "PD10_57") (pintype "passive"))
    )
    (net (code "92") (name "unconnected-(Y1-PD11-Pad58)") (class "Default")
      (node (ref "Y1") (pin "58") (pinfunction "PD11_58") (pintype "passive"))
    )
    (net (code "93") (name "unconnected-(Y1-PD12-Pad59)") (class "Default")
      (node (ref "Y1") (pin "59") (pinfunction "PD12_59") (pintype "passive"))
    )
    (net (code "94") (name "unconnected-(Y1-PE4-Pad3)") (class "Default")
      (node (ref "Y1") (pin "3") (pinfunction "PE4_3") (pintype "passive"))
    )
    (net (code "95") (name "unconnected-(Y1-PE5-Pad4)") (class "Default")
      (node (ref "Y1") (pin "4") (pinfunction "PE5_4") (pintype "passive"))
    )
    (net (code "96") (name "unconnected-(Y1-PE6-Pad5)") (class "Default")
      (node (ref "Y1") (pin "5") (pinfunction "PE6_5") (pintype "passive"))
    )
    (net (code "97") (name "unconnected-(Y1-PE7-Pad38)") (class "Default")
      (node (ref "Y1") (pin "38") (pinfunction "PE7_38") (pintype "passive"))
    )
    (net (code "98") (name "unconnected-(Y1-PE8-Pad39)") (class "Default")
      (node (ref "Y1") (pin "39") (pinfunction "PE8_39") (pintype "passive"))
    )
    (net (code "99") (name "unconnected-(Y1-PE9-Pad40)") (class "Default")
      (node (ref "Y1") (pin "40") (pinfunction "PE9_40") (pintype "passive"))
    )
    (net (code "100") (name "unconnected-(Y1-PE10-Pad41)") (class "Default")
      (node (ref "Y1") (pin "41") (pinfunction "PE10_41") (pintype "passive"))
    )
    (net (code "101") (name "unconnected-(Y1-PE11-Pad42)") (class "Default")
      (node (ref "Y1") (pin "42") (pinfunction "PE11_42") (pintype "passive"))
    )
    (net (code "102") (name "unconnected-(Y1-PE12-Pad43)") (class "Default")
      (node (ref "Y1") (pin "43") (pinfunction "PE12_43") (pintype "passive"))
    )
    (net (code "103") (name "unconnected-(Y1-PE13-Pad44)") (class "Default")
      (node (ref "Y1") (pin "44") (pinfunction "PE13_44") (pintype "passive"))
    )
    (net (code "104") (name "unconnected-(Y1-PE14-Pad45)") (class "Default")
      (node (ref "Y1") (pin "45") (pinfunction "PE14_45") (pintype "passive"))
    )
    (net (code "105") (name "unconnected-(Y1-PE15-Pad46)") (class "Default")
      (node (ref "Y1") (pin "46") (pinfunction "PE15_46") (pintype "passive"))
    )
    (net (code "106") (name "unconnected-(Y1-PH0-OSC_IN-Pad12)") (class "Default")
      (node (ref "Y1") (pin "12") (pinfunction "PH0-OSC_IN_12") (pintype "passive"))
    )
    (net (code "107") (name "unconnected-(Y1-PH1-OSC_OUT-Pad13)") (class "Default")
      (node (ref "Y1") (pin "13") (pinfunction "PH1-OSC_OUT_13") (pintype "passive"))
    )
    (net (code "108") (name "unconnected-(Y1-VBAT-Pad6)") (class "Default")
      (node (ref "Y1") (pin "6") (pinfunction "VBAT_6") (pintype "passive"))
    )
    (net (code "109") (name "unconnected-(Y1-VDDA-Pad22)") (class "Default")
      (node (ref "Y1") (pin "22") (pinfunction "VDDA_22") (pintype "passive"))
    )
    (net (code "110") (name "unconnected-(Y1-VREF+-Pad21)") (class "Default")
      (node (ref "Y1") (pin "21") (pinfunction "VREF+_21") (pintype "passive"))
    )
  )
)
